# SNS_INPUT.net
KiCad netlist of a schematic drawn in Altium Designer
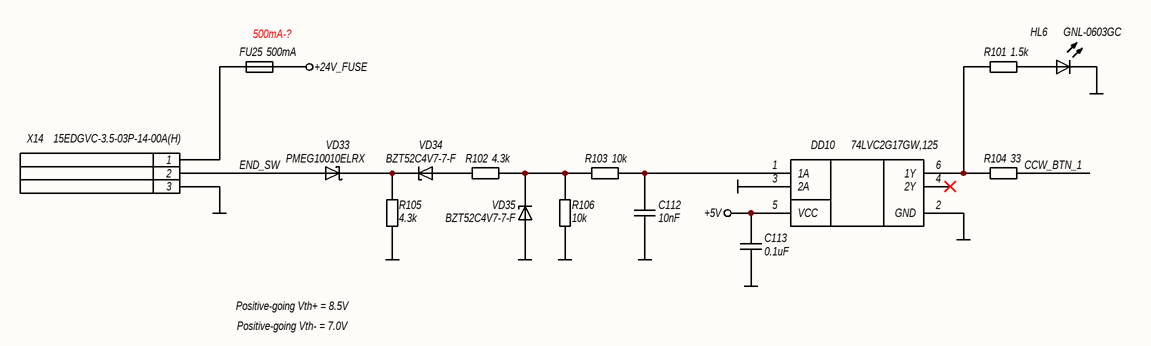
[diagram p0: SNS_INPUT.SchDoc]

(export (version "E")
  (design (tool "Eeschema 10.0.6"))
  (components
    (comp (ref "C112")
      (value "10nF")
      (footprint "C0603N")
      (description "Конденсатор")
      (libsource (lib "Components Library") (part "CAP_FIXED"))
    )
    (comp (ref "C113")
      (value "0.1uF")
      (footprint "C0603N")
      (description "Конденсатор")
      (libsource (lib "Components Library") (part "CAP_FIXED"))
    )
    (comp (ref "DD10")
      (value "74LVC2G17GW,125")
      (footprint "SOT363-2")
      (description "Микросхема сдвоенный триггер Шмитта")
      (libsource (lib "Components Library") (part "74LVC2G17"))
    )
    (comp (ref "FU25")
      (value "500mA")
      (footprint "MF-MSMF")
      (description "Плавкий предохранитель")
      (libsource (lib "Components Library") (part "FUSE"))
    )
    (comp (ref "HL6")
      (value "GNL-0603GC")
      (footprint "LED0603")
      (description "Светодиод")
      (libsource (lib "Components Library") (part "LED"))
    )
    (comp (ref "R101")
      (value "1.5k")
      (footprint "R0603N")
      (description "Резистор")
      (libsource (lib "Components Library") (part "RES_FIXED"))
    )
    (comp (ref "R102")
      (value "4.3k")
      (footprint "R1206N")
      (description "Резистор")
      (libsource (lib "") (part "RES_FIXED_1"))
    )
    (comp (ref "R103")
      (value "10k")
      (footprint "R0603N")
      (description "Резистор")
      (libsource (lib "") (part "RES_FIXED_1"))
    )
    (comp (ref "R104")
      (value "33")
      (footprint "R0603N")
      (description "Резистор")
      (libsource (lib "Components Library") (part "RES_FIXED"))
    )
    (comp (ref "R105")
      (value "4.3k")
      (footprint "R1206N")
      (description "Резистор")
      (libsource (lib "Components Library") (part "RES_FIXED"))
    )
    (comp (ref "R106")
      (value "10k")
      (footprint "R0603N")
      (description "Резистор")
      (libsource (lib "Components Library") (part "RES_FIXED"))
    )
    (comp (ref "VD33")
      (value "PMEG10010ELRX")
      (footprint "SOD123W")
      (description "Диод Шоттки")
      (libsource (lib "Components Library") (part "SCHOTTKY"))
    )
    (comp (ref "VD34")
      (value "BZT52C4V7-7-F")
      (footprint "SOD123")
      (description "Стабилитрон")
      (libsource (lib "Components Library") (part "ZENER"))
    )
    (comp (ref "VD35")
      (value "BZT52C4V7-7-F")
      (footprint "SOD123")
      (description "Стабилитрон")
      (libsource (lib "Components Library") (part "ZENER"))
    )
    (comp (ref "X14")
      (value "15EDGVC-3.5-03P-14-00A(H)")
      (footprint "15EDGVC-3.5-03P-14-00A(H)")
      (description "Разъем, 3 контакта")
      (libsource (lib "Components Library") (part "Connector 3"))
    )
  )
  (nets
    (net (code "1") (name "+5V") (class "Default")
      (node (ref "C113") (pin "2") (pinfunction "2_2") (pintype "passive"))
      (node (ref "DD10") (pin "5") (pinfunction "VCC_5") (pintype "power_in"))
    )
    (net (code "2") (name "+24V_FUSE") (class "Default")
      (node (ref "FU25") (pin "2") (pinfunction "2_2") (pintype "passive"))
    )
    (net (code "3") (name "/CCW_BTN_1") (class "Default")
      (node (ref "R104") (pin "1") (pinfunction "1_1") (pintype "passive"))
    )
    (net (code "4") (name "/END_SW") (class "Default")
      (node (ref "VD33") (pin "2") (pinfunction "A_2") (pintype "passive"))
      (node (ref "X14") (pin "2") (pinfunction "2_2") (pintype "power_in"))
    )
    (net (code "5") (name "GND") (class "Default")
      (node (ref "C112") (pin "2") (pinfunction "2_2") (pintype "passive"))
      (node (ref "C113") (pin "1") (pinfunction "1_1") (pintype "passive"))
      (node (ref "DD10") (pin "2") (pinfunction "GND_2") (pintype "power_in"))
      (node (ref "DD10") (pin "3") (pinfunction "2A_3") (pintype "power_in"))
      (node (ref "HL6") (pin "1") (pinfunction "K_1") (pintype "passive"))
      (node (ref "R105") (pin "2") (pinfunction "2_2") (pintype "passive"))
      (node (ref "R106") (pin "2") (pinfunction "2_2") (pintype "passive"))
      (node (ref "VD35") (pin "2") (pinfunction "A_2") (pintype "passive"))
      (node (ref "X14") (pin "3") (pinfunction "3_3") (pintype "power_in"))
    )
    (net (code "6") (name "Net-(DD10-1A)") (class "Default")
      (node (ref "C112") (pin "1") (pinfunction "1_1") (pintype "passive"))
      (node (ref "DD10") (pin "1") (pinfunction "1A_1") (pintype "power_in"))
      (node (ref "R103") (pin "1") (pinfunction "1_1") (pintype "passive"))
    )
    (net (code "7") (name "Net-(DD10-1Y)") (class "Default")
      (node (ref "DD10") (pin "6") (pinfunction "1Y_6") (pintype "power_in"))
      (node (ref "R101") (pin "2") (pinfunction "2_2") (pintype "passive"))
      (node (ref "R104") (pin "2") (pinfunction "2_2") (pintype "passive"))
    )
    (net (code "8") (name "Net-(FU25-Pad1)") (class "Default")
      (node (ref "FU25") (pin "1") (pinfunction "1_1") (pintype "passive"))
      (node (ref "X14") (pin "1") (pinfunction "1_1") (pintype "power_in"))
    )
    (net (code "9") (name "Net-(HL6-A)") (class "Default")
      (node (ref "HL6") (pin "2") (pinfunction "A_2") (pintype "passive"))
      (node (ref "R101") (pin "1") (pinfunction "1_1") (pintype "passive"))
    )
    (net (code "10") (name "Net-(VD33-K)") (class "Default")
      (node (ref "R105") (pin "1") (pinfunction "1_1") (pintype "passive"))
      (node (ref "VD33") (pin "1") (pinfunction "K_1") (pintype "passive"))
      (node (ref "VD34") (pin "1") (pinfunction "K_1") (pintype "passive"))
    )
    (net (code "11") (name "Net-(VD34-A)") (class "Default")
      (node (ref "R102") (pin "2") (pinfunction "2_2") (pintype "passive"))
      (node (ref "VD34") (pin "2") (pinfunction "A_2") (pintype "passive"))
    )
    (net (code "12") (name "Net-(VD35-K)") (class "Default")
      (node (ref "R102") (pin "1") (pinfunction "1_1") (pintype "passive"))
      (node (ref "R103") (pin "2") (pinfunction "2_2") (pintype "passive"))
      (node (ref "R106") (pin "1") (pinfunction "1_1") (pintype "passive"))
      (node (ref "VD35") (pin "1") (pinfunction "K_1") (pintype "passive"))
    )
    (net (code "13") (name "unconnected-(DD10-2Y-Pad4)") (class "Default")
      (node (ref "DD10") (pin "4") (pinfunction "2Y_4") (pintype "power_in+no_connect"))
    )
  )
)
